# PCB_Sensors.net
KiCad netlist of a schematic drawn in EAGLE
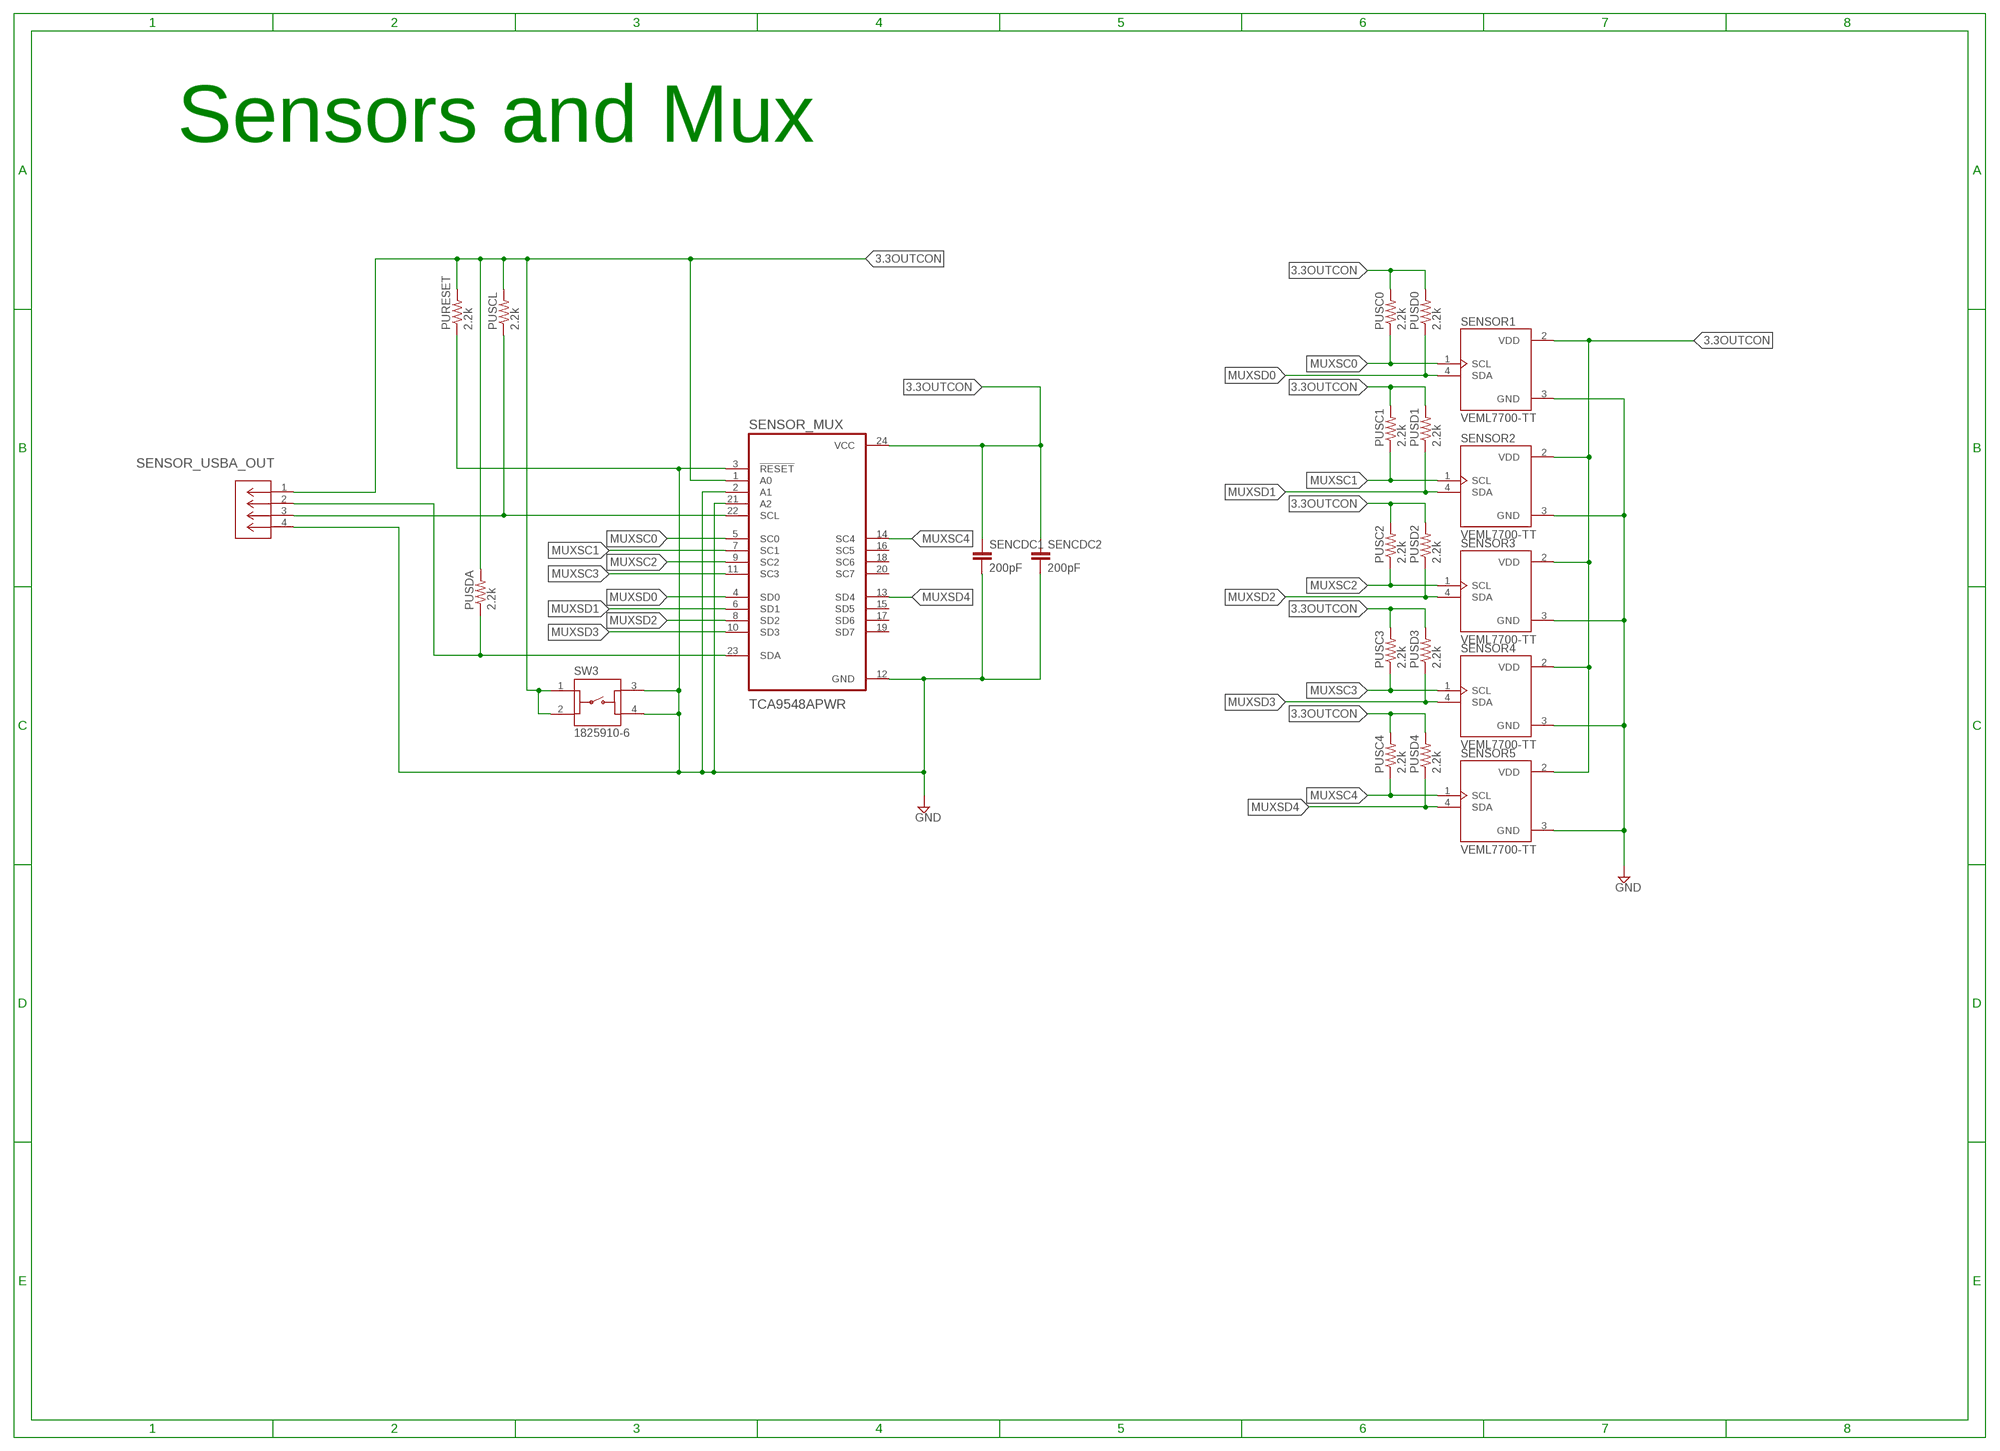
[diagram p0: schematic, sheet 1]

(export (version "E")
  (design (tool "Eeschema 10.0.6"))
  (components
    (comp (ref "PURESET")
      (value "2.2k")
      (footprint "eagle-import:M0805")
      (libsource (lib "eagle-import") (part "R-US_M0805"))
    )
    (comp (ref "PUSC0")
      (value "2.2k")
      (footprint "eagle-import:M0805")
      (libsource (lib "eagle-import") (part "R-US_M0805"))
    )
    (comp (ref "PUSC1")
      (value "2.2k")
      (footprint "eagle-import:M0805")
      (libsource (lib "eagle-import") (part "R-US_M0805"))
    )
    (comp (ref "PUSC2")
      (value "2.2k")
      (footprint "eagle-import:M0805")
      (libsource (lib "eagle-import") (part "R-US_M0805"))
    )
    (comp (ref "PUSC3")
      (value "2.2k")
      (footprint "eagle-import:M0805")
      (libsource (lib "eagle-import") (part "R-US_M0805"))
    )
    (comp (ref "PUSC4")
      (value "2.2k")
      (footprint "eagle-import:M0805")
      (libsource (lib "eagle-import") (part "R-US_M0805"))
    )
    (comp (ref "PUSCL")
      (value "2.2k")
      (footprint "eagle-import:M0805")
      (libsource (lib "eagle-import") (part "R-US_M0805"))
    )
    (comp (ref "PUSD0")
      (value "2.2k")
      (footprint "eagle-import:M0805")
      (libsource (lib "eagle-import") (part "R-US_M0805"))
    )
    (comp (ref "PUSD1")
      (value "2.2k")
      (footprint "eagle-import:M0805")
      (libsource (lib "eagle-import") (part "R-US_M0805"))
    )
    (comp (ref "PUSD2")
      (value "2.2k")
      (footprint "eagle-import:M0805")
      (libsource (lib "eagle-import") (part "R-US_M0805"))
    )
    (comp (ref "PUSD3")
      (value "2.2k")
      (footprint "eagle-import:M0805")
      (libsource (lib "eagle-import") (part "R-US_M0805"))
    )
    (comp (ref "PUSD4")
      (value "2.2k")
      (footprint "eagle-import:M0805")
      (libsource (lib "eagle-import") (part "R-US_M0805"))
    )
    (comp (ref "PUSDA")
      (value "2.2k")
      (footprint "eagle-import:M0805")
      (libsource (lib "eagle-import") (part "R-US_M0805"))
    )
    (comp (ref "SENCDC1")
      (value "200pF")
      (footprint "eagle-import:C0805")
      (libsource (lib "eagle-import") (part "C-EUC0805"))
    )
    (comp (ref "SENCDC2")
      (value "200pF")
      (footprint "eagle-import:C0805")
      (libsource (lib "eagle-import") (part "C-EUC0805"))
    )
    (comp (ref "SENSOR1")
      (value "VEML7700-TT")
      (footprint "eagle-import:XDCR_VEML7700-TT")
      (fields (field (name "MF") "Vishay Semiconductor"))
      (libsource (lib "eagle-import") (part "VEML7700-TT"))
    )
    (comp (ref "SENSOR2")
      (value "VEML7700-TT")
      (footprint "eagle-import:XDCR_VEML7700-TT")
      (fields (field (name "MF") "Vishay Semiconductor"))
      (libsource (lib "eagle-import") (part "VEML7700-TT"))
    )
    (comp (ref "SENSOR3")
      (value "VEML7700-TT")
      (footprint "eagle-import:XDCR_VEML7700-TT")
      (fields (field (name "MF") "Vishay Semiconductor"))
      (libsource (lib "eagle-import") (part "VEML7700-TT"))
    )
    (comp (ref "SENSOR4")
      (value "VEML7700-TT")
      (footprint "eagle-import:XDCR_VEML7700-TT")
      (fields (field (name "MF") "Vishay Semiconductor"))
      (libsource (lib "eagle-import") (part "VEML7700-TT"))
    )
    (comp (ref "SENSOR5")
      (value "VEML7700-TT")
      (footprint "eagle-import:XDCR_VEML7700-TT")
      (fields (field (name "MF") "Vishay Semiconductor"))
      (libsource (lib "eagle-import") (part "VEML7700-TT"))
    )
    (comp (ref "SENSOR_MUX")
      (value "TCA9548APWR")
      (footprint "eagle-import:SOP65P640X120-24N")
      (fields (field (name "MF") "Texas Instruments"))
      (libsource (lib "eagle-import") (part "TCA9548APWR"))
    )
    (comp (ref "SENSOR_USBA_OUT")
      (value "USB-AP-S-RA-SMT")
      (footprint "eagle-import:CONN_USB-AP-S-RA-SMT_ADM")
      (fields (field (name "COPYRIGHT") "Copyright (C) 2023 Ultra Librarian. All rights reserved."))
      (libsource (lib "eagle-import") (part "USB-AP-S-RA-SMT"))
    )
    (comp (ref "SW3")
      (value "1825910-6")
      (footprint "eagle-import:SW_1825910-6-4")
      (fields (field (name "MF") "TE Connectivity"))
      (libsource (lib "eagle-import") (part "1825910-6"))
    )
  )
  (nets
    (net (code "1") (name "3.3OUTCON") (class "Default")
      (node (ref "PURESET") (pin "2") (pinfunction "2_2") (pintype "passive"))
      (node (ref "PUSC0") (pin "2") (pinfunction "2_2") (pintype "passive"))
      (node (ref "PUSC1") (pin "2") (pinfunction "2_2") (pintype "passive"))
      (node (ref "PUSC2") (pin "2") (pinfunction "2_2") (pintype "passive"))
      (node (ref "PUSC3") (pin "2") (pinfunction "2_2") (pintype "passive"))
      (node (ref "PUSC4") (pin "2") (pinfunction "2_2") (pintype "passive"))
      (node (ref "PUSCL") (pin "2") (pinfunction "2_2") (pintype "passive"))
      (node (ref "PUSD0") (pin "2") (pinfunction "2_2") (pintype "passive"))
      (node (ref "PUSD1") (pin "2") (pinfunction "2_2") (pintype "passive"))
      (node (ref "PUSD2") (pin "2") (pinfunction "2_2") (pintype "passive"))
      (node (ref "PUSD3") (pin "2") (pinfunction "2_2") (pintype "passive"))
      (node (ref "PUSD4") (pin "2") (pinfunction "2_2") (pintype "passive"))
      (node (ref "PUSDA") (pin "2") (pinfunction "2_2") (pintype "passive"))
      (node (ref "SENCDC1") (pin "1") (pinfunction "1_1") (pintype "passive"))
      (node (ref "SENCDC2") (pin "1") (pinfunction "1_1") (pintype "passive"))
      (node (ref "SENSOR1") (pin "2") (pinfunction "VDD_2") (pintype "power_in"))
      (node (ref "SENSOR2") (pin "2") (pinfunction "VDD_2") (pintype "power_in"))
      (node (ref "SENSOR3") (pin "2") (pinfunction "VDD_2") (pintype "power_in"))
      (node (ref "SENSOR4") (pin "2") (pinfunction "VDD_2") (pintype "power_in"))
      (node (ref "SENSOR5") (pin "2") (pinfunction "VDD_2") (pintype "power_in"))
      (node (ref "SENSOR_MUX") (pin "1") (pinfunction "A0_1") (pintype "input"))
      (node (ref "SENSOR_MUX") (pin "24") (pinfunction "VCC_24") (pintype "power_in"))
      (node (ref "SENSOR_USBA_OUT") (pin "1") (pinfunction "1_1") (pintype "passive"))
      (node (ref "SW3") (pin "1") (pinfunction "1_1") (pintype "passive"))
      (node (ref "SW3") (pin "2") (pinfunction "2_2") (pintype "passive"))
    )
    (net (code "2") (name "GND") (class "Default")
      (node (ref "PURESET") (pin "1") (pinfunction "1_1") (pintype "passive"))
      (node (ref "SENCDC1") (pin "2") (pinfunction "2_2") (pintype "passive"))
      (node (ref "SENCDC2") (pin "2") (pinfunction "2_2") (pintype "passive"))
      (node (ref "SENSOR1") (pin "3") (pinfunction "GND_3") (pintype "power_in"))
      (node (ref "SENSOR2") (pin "3") (pinfunction "GND_3") (pintype "power_in"))
      (node (ref "SENSOR3") (pin "3") (pinfunction "GND_3") (pintype "power_in"))
      (node (ref "SENSOR4") (pin "3") (pinfunction "GND_3") (pintype "power_in"))
      (node (ref "SENSOR5") (pin "3") (pinfunction "GND_3") (pintype "power_in"))
      (node (ref "SENSOR_MUX") (pin "12") (pinfunction "GND_12") (pintype "power_in"))
      (node (ref "SENSOR_MUX") (pin "2") (pinfunction "A1_2") (pintype "input"))
      (node (ref "SENSOR_MUX") (pin "21") (pinfunction "A2_21") (pintype "input"))
      (node (ref "SENSOR_MUX") (pin "3") (pinfunction "~{RESET}_3") (pintype "input"))
      (node (ref "SENSOR_USBA_OUT") (pin "4") (pinfunction "4_4") (pintype "passive"))
      (node (ref "SW3") (pin "3") (pinfunction "3_3") (pintype "passive"))
      (node (ref "SW3") (pin "4") (pinfunction "4_4") (pintype "passive"))
    )
    (net (code "3") (name "MUXSC0") (class "Default")
      (node (ref "PUSC0") (pin "1") (pinfunction "1_1") (pintype "passive"))
      (node (ref "SENSOR1") (pin "1") (pinfunction "SCL_1") (pintype "input"))
      (node (ref "SENSOR_MUX") (pin "5") (pinfunction "SC0_5") (pintype "bidirectional"))
    )
    (net (code "4") (name "MUXSC1") (class "Default")
      (node (ref "PUSC1") (pin "1") (pinfunction "1_1") (pintype "passive"))
      (node (ref "SENSOR2") (pin "1") (pinfunction "SCL_1") (pintype "input"))
      (node (ref "SENSOR_MUX") (pin "7") (pinfunction "SC1_7") (pintype "bidirectional"))
    )
    (net (code "5") (name "MUXSC2") (class "Default")
      (node (ref "PUSC2") (pin "1") (pinfunction "1_1") (pintype "passive"))
      (node (ref "SENSOR3") (pin "1") (pinfunction "SCL_1") (pintype "input"))
      (node (ref "SENSOR_MUX") (pin "9") (pinfunction "SC2_9") (pintype "bidirectional"))
    )
    (net (code "6") (name "MUXSC3") (class "Default")
      (node (ref "PUSC3") (pin "1") (pinfunction "1_1") (pintype "passive"))
      (node (ref "SENSOR4") (pin "1") (pinfunction "SCL_1") (pintype "input"))
      (node (ref "SENSOR_MUX") (pin "11") (pinfunction "SC3_11") (pintype "bidirectional"))
    )
    (net (code "7") (name "MUXSC4") (class "Default")
      (node (ref "PUSC4") (pin "1") (pinfunction "1_1") (pintype "passive"))
      (node (ref "SENSOR5") (pin "1") (pinfunction "SCL_1") (pintype "input"))
      (node (ref "SENSOR_MUX") (pin "14") (pinfunction "SC4_14") (pintype "bidirectional"))
    )
    (net (code "8") (name "MUXSD0") (class "Default")
      (node (ref "PUSD0") (pin "1") (pinfunction "1_1") (pintype "passive"))
      (node (ref "SENSOR1") (pin "4") (pinfunction "SDA_4") (pintype "bidirectional"))
      (node (ref "SENSOR_MUX") (pin "4") (pinfunction "SD0_4") (pintype "bidirectional"))
    )
    (net (code "9") (name "MUXSD1") (class "Default")
      (node (ref "PUSD1") (pin "1") (pinfunction "1_1") (pintype "passive"))
      (node (ref "SENSOR2") (pin "4") (pinfunction "SDA_4") (pintype "bidirectional"))
      (node (ref "SENSOR_MUX") (pin "6") (pinfunction "SD1_6") (pintype "bidirectional"))
    )
    (net (code "10") (name "MUXSD2") (class "Default")
      (node (ref "PUSD2") (pin "1") (pinfunction "1_1") (pintype "passive"))
      (node (ref "SENSOR3") (pin "4") (pinfunction "SDA_4") (pintype "bidirectional"))
      (node (ref "SENSOR_MUX") (pin "8") (pinfunction "SD2_8") (pintype "bidirectional"))
    )
    (net (code "11") (name "MUXSD3") (class "Default")
      (node (ref "PUSD3") (pin "1") (pinfunction "1_1") (pintype "passive"))
      (node (ref "SENSOR4") (pin "4") (pinfunction "SDA_4") (pintype "bidirectional"))
      (node (ref "SENSOR_MUX") (pin "10") (pinfunction "SD3_10") (pintype "bidirectional"))
    )
    (net (code "12") (name "MUXSD4") (class "Default")
      (node (ref "PUSD4") (pin "1") (pinfunction "1_1") (pintype "passive"))
      (node (ref "SENSOR5") (pin "4") (pinfunction "SDA_4") (pintype "bidirectional"))
      (node (ref "SENSOR_MUX") (pin "13") (pinfunction "SD4_13") (pintype "bidirectional"))
    )
    (net (code "13") (name "Net-(SENSOR_MUX-SCL)") (class "Default")
      (node (ref "PUSCL") (pin "1") (pinfunction "1_1") (pintype "passive"))
      (node (ref "SENSOR_MUX") (pin "22") (pinfunction "SCL_22") (pintype "input"))
      (node (ref "SENSOR_USBA_OUT") (pin "3") (pinfunction "3_3") (pintype "passive"))
    )
    (net (code "14") (name "Net-(SENSOR_MUX-SDA)") (class "Default")
      (node (ref "PUSDA") (pin "1") (pinfunction "1_1") (pintype "passive"))
      (node (ref "SENSOR_MUX") (pin "23") (pinfunction "SDA_23") (pintype "bidirectional"))
      (node (ref "SENSOR_USBA_OUT") (pin "2") (pinfunction "2_2") (pintype "passive"))
    )
    (net (code "15") (name "unconnected-(SENSOR_MUX-SC5-Pad16)") (class "Default")
      (node (ref "SENSOR_MUX") (pin "16") (pinfunction "SC5_16") (pintype "bidirectional"))
    )
    (net (code "16") (name "unconnected-(SENSOR_MUX-SC6-Pad18)") (class "Default")
      (node (ref "SENSOR_MUX") (pin "18") (pinfunction "SC6_18") (pintype "bidirectional"))
    )
    (net (code "17") (name "unconnected-(SENSOR_MUX-SC7-Pad20)") (class "Default")
      (node (ref "SENSOR_MUX") (pin "20") (pinfunction "SC7_20") (pintype "bidirectional"))
    )
    (net (code "18") (name "unconnected-(SENSOR_MUX-SD5-Pad15)") (class "Default")
      (node (ref "SENSOR_MUX") (pin "15") (pinfunction "SD5_15") (pintype "bidirectional"))
    )
    (net (code "19") (name "unconnected-(SENSOR_MUX-SD6-Pad17)") (class "Default")
      (node (ref "SENSOR_MUX") (pin "17") (pinfunction "SD6_17") (pintype "bidirectional"))
    )
    (net (code "20") (name "unconnected-(SENSOR_MUX-SD7-Pad19)") (class "Default")
      (node (ref "SENSOR_MUX") (pin "19") (pinfunction "SD7_19") (pintype "bidirectional"))
    )
  )
)
